# DC_DC_Convertor.net
KiCad netlist of a schematic drawn in Altium Designer
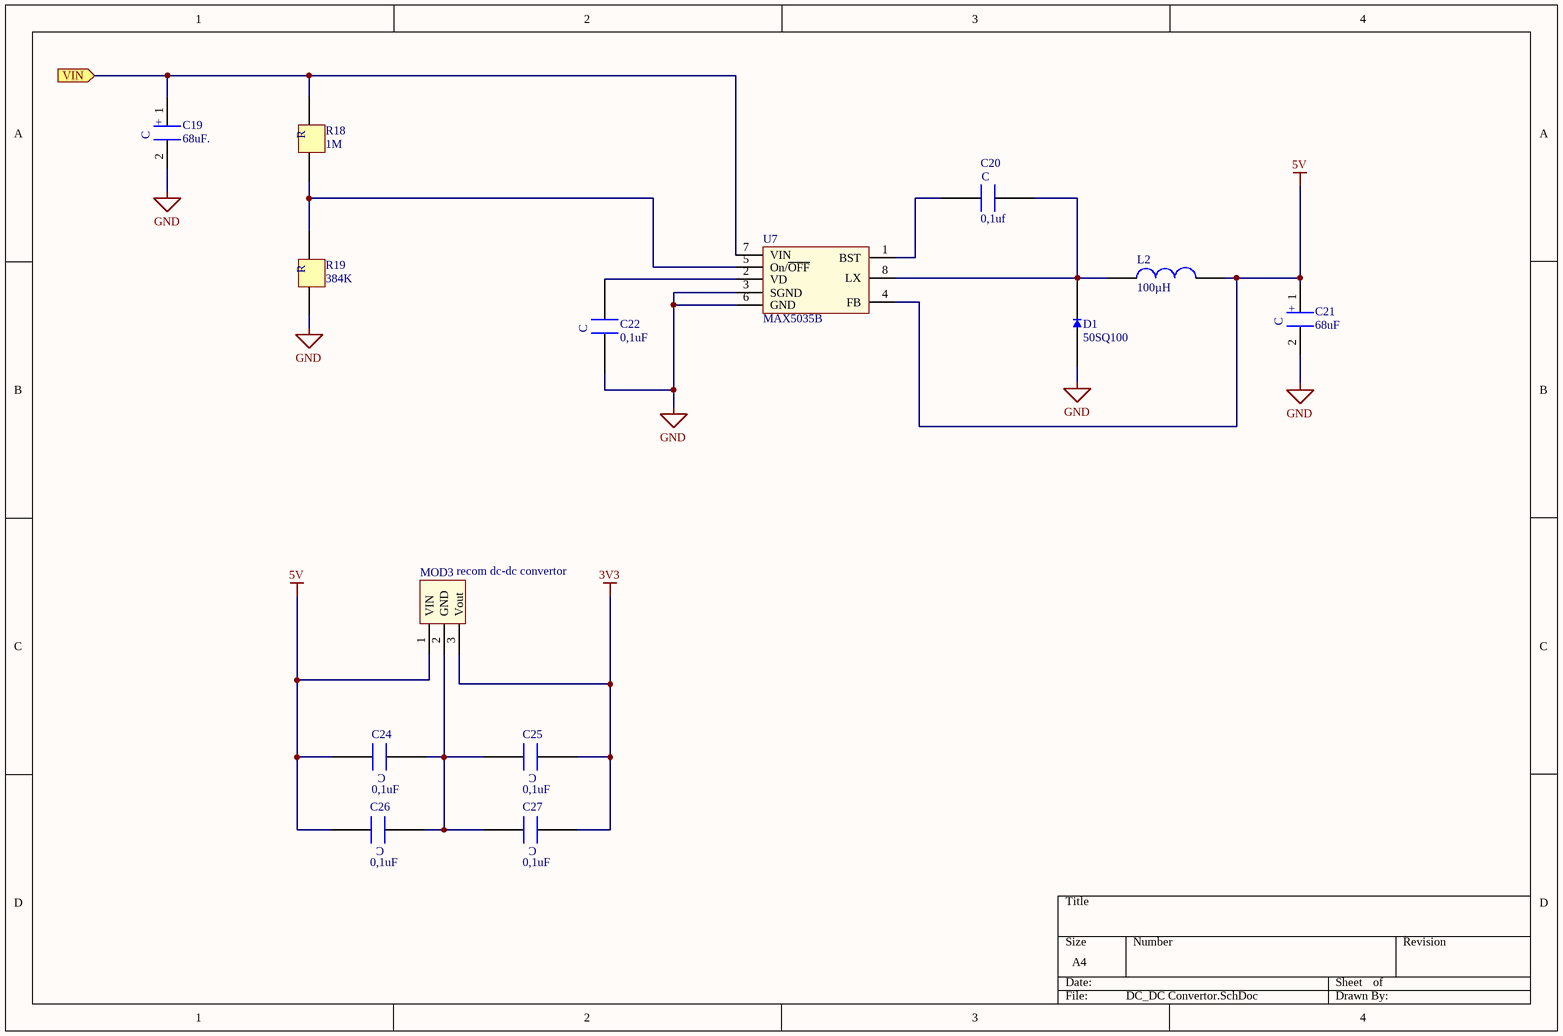
[diagram p0: DC_DC Convertor.SchDoc]

(export (version "E")
  (design (tool "Eeschema 10.0.6"))
  (components
    (comp (ref "C19") (value "68uF.") (libsource (lib "pasives") (part "cap_pol")))
    (comp (ref "C20") (value "0,1uf") (footprint "0603") (libsource (lib "pasives") (part "capacitor")))
    (comp (ref "C21") (value "68uF") (libsource (lib "pasives") (part "cap_pol")))
    (comp (ref "C22")
      (value "0,1uF")
      (footprint "CAPC1005X04L")
      (libsource (lib "pasives") (part "capacitor"))
    )
    (comp (ref "C24") (value "0,1uF") (footprint "0603") (libsource (lib "pasives") (part "capacitor")))
    (comp (ref "C25") (value "0,1uF") (footprint "0603") (libsource (lib "pasives") (part "capacitor")))
    (comp (ref "C26") (value "0,1uF") (footprint "0603") (libsource (lib "pasives") (part "capacitor")))
    (comp (ref "C27") (value "0,1uF") (footprint "0603") (libsource (lib "pasives") (part "capacitor")))
    (comp (ref "D1")
      (value "50SQ100")
      (footprint "TROUGH HOLE DIODE")
      (libsource (lib "halfgelijders") (part "diode"))
    )
    (comp (ref "L2")
      (value "100µH")
      (footprint "Coilcraft , XFL4020-102")
      (libsource (lib "pasives") (part "Spoel"))
    )
    (comp (ref "MOD3")
      (value "recom dc-dc convertor")
      (libsource (lib "halfgelijders") (part "recom dc-dc convertor"))
    )
    (comp (ref "R18") (value "1M") (footprint "0603") (libsource (lib "pasives") (part "resistor")))
    (comp (ref "R19") (value "384K") (footprint "0603") (libsource (lib "pasives") (part "resistor")))
    (comp (ref "U7")
      (value "MAX5035B")
      (footprint "SOICN8")
      (libsource (lib "halfgelijders") (part "MAX5035"))
    )
  )
  (nets
    (net (code "1") (name "/VIN") (class "Default")
      (node (ref "C19") (pin "1") (pinfunction "1_1") (pintype "passive"))
      (node (ref "R18") (pin "1") (pinfunction "1_1") (pintype "passive"))
      (node (ref "U7") (pin "7") (pinfunction "VIN_7") (pintype "power_in"))
    )
    (net (code "2") (name "3V3") (class "Default")
      (node (ref "C25") (pin "2") (pinfunction "2_2") (pintype "passive"))
      (node (ref "C27") (pin "2") (pinfunction "2_2") (pintype "passive"))
      (node (ref "MOD3") (pin "3") (pinfunction "Vout_3") (pintype "passive"))
    )
    (net (code "3") (name "5V") (class "Default")
      (node (ref "C21") (pin "1") (pinfunction "1_1") (pintype "passive"))
      (node (ref "C24") (pin "1") (pinfunction "1_1") (pintype "passive"))
      (node (ref "C26") (pin "1") (pinfunction "1_1") (pintype "passive"))
      (node (ref "L2") (pin "1") (pinfunction "1_1") (pintype "passive"))
      (node (ref "MOD3") (pin "1") (pinfunction "VIN_1") (pintype "passive"))
      (node (ref "U7") (pin "4") (pinfunction "FB_4") (pintype "passive"))
    )
    (net (code "4") (name "GND") (class "Default")
      (node (ref "C19") (pin "2") (pinfunction "2_2") (pintype "passive"))
      (node (ref "C21") (pin "2") (pinfunction "2_2") (pintype "passive"))
      (node (ref "C22") (pin "2") (pinfunction "2_2") (pintype "passive"))
      (node (ref "D1") (pin "1") (pinfunction "1_1") (pintype "passive"))
      (node (ref "R19") (pin "2") (pinfunction "2_2") (pintype "passive"))
      (node (ref "U7") (pin "3") (pinfunction "SGND_3") (pintype "power_in"))
      (node (ref "U7") (pin "6") (pinfunction "GND_6") (pintype "passive"))
    )
    (net (code "5") (name "Net-(MOD3-GND)") (class "Default")
      (node (ref "C24") (pin "2") (pinfunction "2_2") (pintype "passive"))
      (node (ref "C25") (pin "1") (pinfunction "1_1") (pintype "passive"))
      (node (ref "C26") (pin "2") (pinfunction "2_2") (pintype "passive"))
      (node (ref "C27") (pin "1") (pinfunction "1_1") (pintype "passive"))
      (node (ref "MOD3") (pin "2") (pinfunction "GND_2") (pintype "passive"))
    )
    (net (code "6") (name "Net-(U7-BST)") (class "Default")
      (node (ref "C20") (pin "2") (pinfunction "2_2") (pintype "passive"))
      (node (ref "U7") (pin "1") (pinfunction "BST_1") (pintype "passive"))
    )
    (net (code "7") (name "Net-(U7-LX)") (class "Default")
      (node (ref "C20") (pin "1") (pinfunction "1_1") (pintype "passive"))
      (node (ref "D1") (pin "2") (pinfunction "2_2") (pintype "passive"))
      (node (ref "L2") (pin "2") (pinfunction "2_2") (pintype "passive"))
      (node (ref "U7") (pin "8") (pinfunction "LX_8") (pintype "passive"))
    )
    (net (code "8") (name "Net-(U7-On{slash}~{OFF})") (class "Default")
      (node (ref "R18") (pin "2") (pinfunction "2_2") (pintype "passive"))
      (node (ref "R19") (pin "1") (pinfunction "1_1") (pintype "passive"))
      (node (ref "U7") (pin "5") (pinfunction "On/~{OFF}_5") (pintype "passive"))
    )
    (net (code "9") (name "Net-(U7-VD)") (class "Default")
      (node (ref "C22") (pin "1") (pinfunction "1_1") (pintype "passive"))
      (node (ref "U7") (pin "2") (pinfunction "VD_2") (pintype "passive"))
    )
  )
)
